# nutnhanguyen_ly_A.net
KiCad netlist of a schematic drawn in Altium Designer
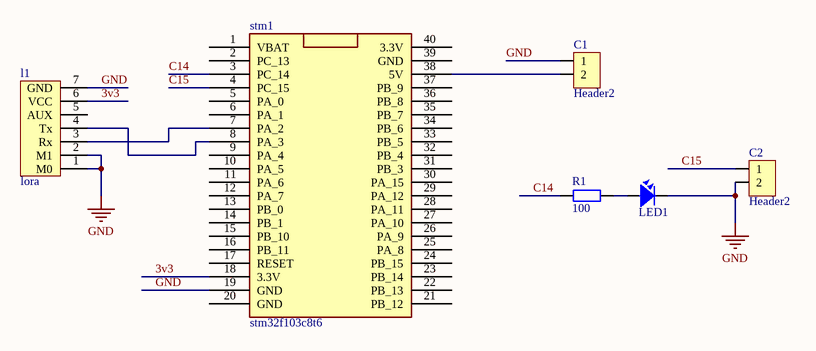
[diagram p0: nutnhanguyen ly A.SchDoc]

(export (version "E")
  (design (tool "Eeschema 10.0.6"))
  (components
    (comp (ref "C1")
      (value "Header2")
      (footprint "Header2")
      (description "Header IDC, 2 x 1 Pin Vertical 2.54mm Pitch (Non-Boxed, Male)")
      (fields
        (field (name "MANUFACTURER") "Würth Elektronik eiSos GmbH")
        (field (name "PARTNO") "613002143121")
        (field (name "CREATED BY") "Karrer Zheng")
      )
      (libsource (lib "LIBRARY1") (part "Header2"))
    )
    (comp (ref "C2")
      (value "Header2")
      (footprint "Header2")
      (description "Header IDC, 2 x 1 Pin Vertical 2.54mm Pitch (Non-Boxed, Male)")
      (fields
        (field (name "MANUFACTURER") "Würth Elektronik eiSos GmbH")
        (field (name "PARTNO") "613002143121")
        (field (name "CREATED BY") "Karrer Zheng")
      )
      (libsource (lib "LIBRARY1") (part "Header2"))
    )
    (comp (ref "l1")
      (value "lora")
      (footprint "lora sx1278")
      (libsource (lib "link kien_thien") (part "lora SX1278"))
    )
    (comp (ref "LED1")
      (value "LED")
      (footprint "LED-5-RED")
      (description "LED Single colour Green and Red")
      (libsource (lib "LIBRARY1") (part "LED"))
    )
    (comp (ref "R1")
      (value "100")
      (footprint "R1/4W")
      (description "Resistor 1/4W")
      (libsource (lib "My Library") (part "R1/4W"))
    )
    (comp (ref "stm1")
      (value "stm32f103c8t6")
      (footprint "40chan")
      (libsource (lib "link kien_thien") (part "stm32f103c8t6"))
    )
  )
  (nets
    (net (code "1") (name "/3v3") (class "Default")
      (node (ref "l1") (pin "6") (pinfunction "VCC_6") (pintype "passive"))
      (node (ref "stm1") (pin "18") (pinfunction "3.3V_18") (pintype "passive"))
    )
    (net (code "2") (name "/C14") (class "Default")
      (node (ref "R1") (pin "1") (pinfunction "1_1") (pintype "passive"))
      (node (ref "stm1") (pin "3") (pinfunction "PC_14_3") (pintype "passive"))
    )
    (net (code "3") (name "/C15") (class "Default")
      (node (ref "C2") (pin "1") (pinfunction "1_1") (pintype "passive"))
      (node (ref "stm1") (pin "4") (pinfunction "PC_15_4") (pintype "passive"))
    )
    (net (code "4") (name "GND") (class "Default")
      (node (ref "C1") (pin "1") (pinfunction "1_1") (pintype "passive"))
      (node (ref "C2") (pin "2") (pinfunction "2_2") (pintype "passive"))
      (node (ref "LED1") (pin "2") (pinfunction "2_2") (pintype "passive"))
      (node (ref "l1") (pin "1") (pinfunction "M0_1") (pintype "passive"))
      (node (ref "l1") (pin "2") (pinfunction "M1_2") (pintype "passive"))
      (node (ref "l1") (pin "7") (pinfunction "GND_7") (pintype "passive"))
      (node (ref "stm1") (pin "19") (pinfunction "GND_19") (pintype "passive"))
    )
    (net (code "5") (name "Net-(LED1-Pad1)") (class "Default")
      (node (ref "LED1") (pin "1") (pinfunction "1_1") (pintype "passive"))
      (node (ref "R1") (pin "2") (pinfunction "2_2") (pintype "passive"))
    )
    (net (code "6") (name "Net-(l1-Rx)") (class "Default")
      (node (ref "l1") (pin "3") (pinfunction "Rx_3") (pintype "passive"))
      (node (ref "stm1") (pin "7") (pinfunction "PA_2_7") (pintype "passive"))
    )
    (net (code "7") (name "Net-(l1-Tx)") (class "Default")
      (node (ref "l1") (pin "4") (pinfunction "Tx_4") (pintype "passive"))
      (node (ref "stm1") (pin "8") (pinfunction "PA_3_8") (pintype "passive"))
    )
    (net (code "8") (name "Net-(stm1-5V)") (class "Default")
      (node (ref "C1") (pin "2") (pinfunction "2_2") (pintype "passive"))
      (node (ref "stm1") (pin "38") (pinfunction "5V_38") (pintype "passive"))
    )
    (net (code "9") (name "unconnected-(l1-AUX-Pad5)") (class "Default")
      (node (ref "l1") (pin "5") (pinfunction "AUX_5") (pintype "passive"))
    )
    (net (code "10") (name "unconnected-(stm1-3.3V-Pad40)") (class "Default")
      (node (ref "stm1") (pin "40") (pinfunction "3.3V_40") (pintype "passive"))
    )
    (net (code "11") (name "unconnected-(stm1-GND-Pad20)") (class "Default")
      (node (ref "stm1") (pin "20") (pinfunction "GND_20") (pintype "passive"))
    )
    (net (code "12") (name "unconnected-(stm1-GND-Pad39)") (class "Default")
      (node (ref "stm1") (pin "39") (pinfunction "GND_39") (pintype "passive"))
    )
    (net (code "13") (name "unconnected-(stm1-PA_0-Pad5)") (class "Default")
      (node (ref "stm1") (pin "5") (pinfunction "PA_0_5") (pintype "passive"))
    )
    (net (code "14") (name "unconnected-(stm1-PA_1-Pad6)") (class "Default")
      (node (ref "stm1") (pin "6") (pinfunction "PA_1_6") (pintype "passive"))
    )
    (net (code "15") (name "unconnected-(stm1-PA_4-Pad9)") (class "Default")
      (node (ref "stm1") (pin "9") (pinfunction "PA_4_9") (pintype "passive"))
    )
    (net (code "16") (name "unconnected-(stm1-PA_5-Pad10)") (class "Default")
      (node (ref "stm1") (pin "10") (pinfunction "PA_5_10") (pintype "passive"))
    )
    (net (code "17") (name "unconnected-(stm1-PA_6-Pad11)") (class "Default")
      (node (ref "stm1") (pin "11") (pinfunction "PA_6_11") (pintype "passive"))
    )
    (net (code "18") (name "unconnected-(stm1-PA_7-Pad12)") (class "Default")
      (node (ref "stm1") (pin "12") (pinfunction "PA_7_12") (pintype "passive"))
    )
    (net (code "19") (name "unconnected-(stm1-PA_8-Pad25)") (class "Default")
      (node (ref "stm1") (pin "25") (pinfunction "PA_8_25") (pintype "passive"))
    )
    (net (code "20") (name "unconnected-(stm1-PA_9-Pad26)") (class "Default")
      (node (ref "stm1") (pin "26") (pinfunction "PA_9_26") (pintype "passive"))
    )
    (net (code "21") (name "unconnected-(stm1-PA_10-Pad27)") (class "Default")
      (node (ref "stm1") (pin "27") (pinfunction "PA_10_27") (pintype "passive"))
    )
    (net (code "22") (name "unconnected-(stm1-PA_11-Pad28)") (class "Default")
      (node (ref "stm1") (pin "28") (pinfunction "PA_11_28") (pintype "passive"))
    )
    (net (code "23") (name "unconnected-(stm1-PA_12-Pad29)") (class "Default")
      (node (ref "stm1") (pin "29") (pinfunction "PA_12_29") (pintype "passive"))
    )
    (net (code "24") (name "unconnected-(stm1-PA_15-Pad30)") (class "Default")
      (node (ref "stm1") (pin "30") (pinfunction "PA_15_30") (pintype "passive"))
    )
    (net (code "25") (name "unconnected-(stm1-PB_0-Pad13)") (class "Default")
      (node (ref "stm1") (pin "13") (pinfunction "PB_0_13") (pintype "passive"))
    )
    (net (code "26") (name "unconnected-(stm1-PB_1-Pad14)") (class "Default")
      (node (ref "stm1") (pin "14") (pinfunction "PB_1_14") (pintype "passive"))
    )
    (net (code "27") (name "unconnected-(stm1-PB_3-Pad31)") (class "Default")
      (node (ref "stm1") (pin "31") (pinfunction "PB_3_31") (pintype "passive"))
    )
    (net (code "28") (name "unconnected-(stm1-PB_4-Pad32)") (class "Default")
      (node (ref "stm1") (pin "32") (pinfunction "PB_4_32") (pintype "passive"))
    )
    (net (code "29") (name "unconnected-(stm1-PB_5-Pad33)") (class "Default")
      (node (ref "stm1") (pin "33") (pinfunction "PB_5_33") (pintype "passive"))
    )
    (net (code "30") (name "unconnected-(stm1-PB_6-Pad34)") (class "Default")
      (node (ref "stm1") (pin "34") (pinfunction "PB_6_34") (pintype "passive"))
    )
    (net (code "31") (name "unconnected-(stm1-PB_7-Pad35)") (class "Default")
      (node (ref "stm1") (pin "35") (pinfunction "PB_7_35") (pintype "passive"))
    )
    (net (code "32") (name "unconnected-(stm1-PB_8-Pad36)") (class "Default")
      (node (ref "stm1") (pin "36") (pinfunction "PB_8_36") (pintype "passive"))
    )
    (net (code "33") (name "unconnected-(stm1-PB_9-Pad37)") (class "Default")
      (node (ref "stm1") (pin "37") (pinfunction "PB_9_37") (pintype "passive"))
    )
    (net (code "34") (name "unconnected-(stm1-PB_10-Pad15)") (class "Default")
      (node (ref "stm1") (pin "15") (pinfunction "PB_10_15") (pintype "passive"))
    )
    (net (code "35") (name "unconnected-(stm1-PB_11-Pad16)") (class "Default")
      (node (ref "stm1") (pin "16") (pinfunction "PB_11_16") (pintype "passive"))
    )
    (net (code "36") (name "unconnected-(stm1-PB_12-Pad21)") (class "Default")
      (node (ref "stm1") (pin "21") (pinfunction "PB_12_21") (pintype "passive"))
    )
    (net (code "37") (name "unconnected-(stm1-PB_13-Pad22)") (class "Default")
      (node (ref "stm1") (pin "22") (pinfunction "PB_13_22") (pintype "passive"))
    )
    (net (code "38") (name "unconnected-(stm1-PB_14-Pad23)") (class "Default")
      (node (ref "stm1") (pin "23") (pinfunction "PB_14_23") (pintype "passive"))
    )
    (net (code "39") (name "unconnected-(stm1-PB_15-Pad24)") (class "Default")
      (node (ref "stm1") (pin "24") (pinfunction "PB_15_24") (pintype "passive"))
    )
    (net (code "40") (name "unconnected-(stm1-PC_13-Pad2)") (class "Default")
      (node (ref "stm1") (pin "2") (pinfunction "PC_13_2") (pintype "passive"))
    )
    (net (code "41") (name "unconnected-(stm1-RESET-Pad17)") (class "Default")
      (node (ref "stm1") (pin "17") (pinfunction "RESET_17") (pintype "passive"))
    )
    (net (code "42") (name "unconnected-(stm1-VBAT-Pad1)") (class "Default")
      (node (ref "stm1") (pin "1") (pinfunction "VBAT_1") (pintype "passive"))
    )
  )
)
